# PSSchematic.net
KiCad netlist of a schematic drawn in Altium Designer
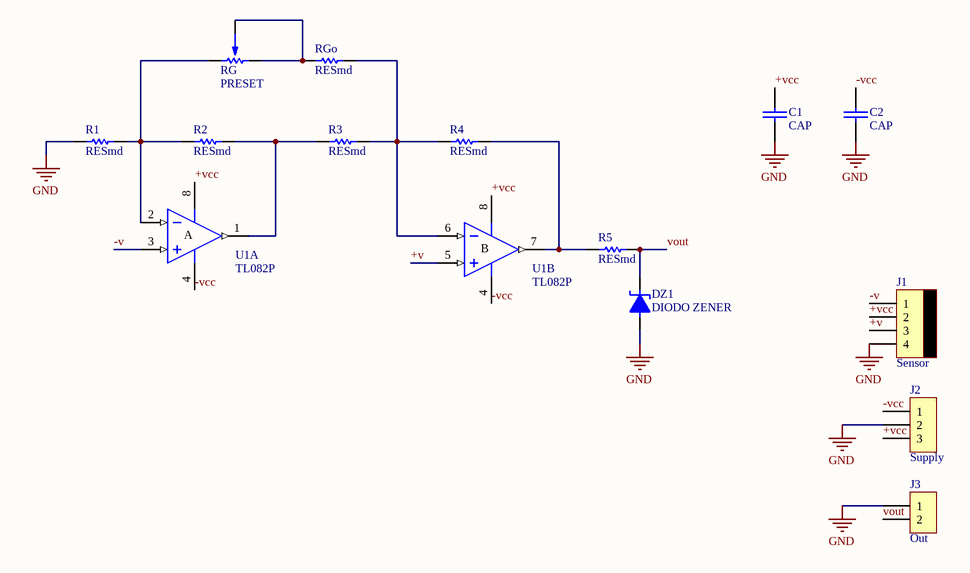
[diagram p0: PSSchematic.SchDoc]

(export (version "E")
  (design (tool "Eeschema 10.0.6"))
  (components
    (comp (ref "C1") (value "CAP") (footprint "CAP100") (libsource (lib "LIBEBAL") (part "CAP")))
    (comp (ref "C2") (value "CAP") (footprint "CAP100") (libsource (lib "LIBEBAL") (part "CAP")))
    (comp (ref "DZ1")
      (value "DIODO ZENER")
      (footprint "DO41")
      (libsource (lib "LIBEBAL") (part "DIODO ZENER"))
    )
    (comp (ref "J1") (value "Sensor") (footprint "MOLEX4") (libsource (lib "LIBEBAL") (part "MOLEX4")))
    (comp (ref "J2") (value "Supply") (footprint "BORNERA3") (libsource (lib "LIBEBAL") (part "BORNERA 3")))
    (comp (ref "J3") (value "Out") (footprint "BORNERA2") (libsource (lib "LIBEBAL") (part "BORNERA 2")))
    (comp (ref "R1") (value "RESmd") (footprint "0805") (libsource (lib "LIBEBAL") (part "RES")))
    (comp (ref "R2") (value "RESmd") (footprint "0805") (libsource (lib "LIBEBAL") (part "RES")))
    (comp (ref "R3") (value "RESmd") (footprint "0805") (libsource (lib "LIBEBAL") (part "RES")))
    (comp (ref "R4") (value "RESmd") (footprint "0805") (libsource (lib "LIBEBAL") (part "RES")))
    (comp (ref "R5") (value "RESmd") (footprint "0805") (libsource (lib "LIBEBAL") (part "RES")))
    (comp (ref "RG") (value "PRESET") (footprint "PRESET V") (libsource (lib "LIBEBAL") (part "PRESET")))
    (comp (ref "RGo") (value "RESmd") (footprint "0805") (libsource (lib "LIBEBAL") (part "RES")))
    (comp (ref "U1")
      (value "TL082P")
      (footprint "P008")
      (description "JFET-Input Operational Amplifier")
      (fields (field (name "PUBLISHER") "Altium Limited"))
      (libsource (lib "TI Operational Amplifier") (part "TL082P"))
    )
  )
  (nets
    (net (code "1") (name "/+v") (class "Default")
      (node (ref "J1") (pin "3") (pinfunction "3_3") (pintype "passive"))
      (node (ref "U1") (pin "5") (pinfunction "IN+_5") (pintype "input"))
    )
    (net (code "2") (name "/+vcc") (class "Default")
      (node (ref "C1") (pin "1") (pinfunction "1_1") (pintype "passive"))
      (node (ref "J1") (pin "2") (pinfunction "2_2") (pintype "passive"))
      (node (ref "J2") (pin "3") (pinfunction "3_3") (pintype "passive"))
      (node (ref "U1") (pin "8") (pinfunction "V+_8") (pintype "power_in"))
    )
    (net (code "3") (name "/-v") (class "Default")
      (node (ref "J1") (pin "1") (pinfunction "1_1") (pintype "passive"))
      (node (ref "U1") (pin "3") (pinfunction "IN+_3") (pintype "input"))
    )
    (net (code "4") (name "/-vcc") (class "Default")
      (node (ref "C2") (pin "1") (pinfunction "1_1") (pintype "passive"))
      (node (ref "J2") (pin "1") (pinfunction "1_1") (pintype "passive"))
      (node (ref "U1") (pin "4") (pinfunction "V-_4") (pintype "power_in"))
    )
    (net (code "5") (name "/vout") (class "Default")
      (node (ref "DZ1") (pin "2") (pinfunction "2_2") (pintype "passive"))
      (node (ref "J3") (pin "2") (pinfunction "2_2") (pintype "passive"))
      (node (ref "R5") (pin "2") (pinfunction "2_2") (pintype "passive"))
    )
    (net (code "6") (name "GND") (class "Default")
      (node (ref "C1") (pin "2") (pinfunction "2_2") (pintype "passive"))
      (node (ref "C2") (pin "2") (pinfunction "2_2") (pintype "passive"))
      (node (ref "DZ1") (pin "1") (pinfunction "1_1") (pintype "passive"))
      (node (ref "J1") (pin "4") (pinfunction "4_4") (pintype "passive"))
      (node (ref "J2") (pin "2") (pinfunction "2_2") (pintype "passive"))
      (node (ref "J3") (pin "1") (pinfunction "1_1") (pintype "passive"))
      (node (ref "R1") (pin "1") (pinfunction "1_1") (pintype "passive"))
    )
    (net (code "7") (name "Net-(RG-Pad2)") (class "Default")
      (node (ref "RG") (pin "2") (pinfunction "2_2") (pintype "passive"))
      (node (ref "RG") (pin "3") (pinfunction "3_3") (pintype "passive"))
      (node (ref "RGo") (pin "1") (pinfunction "1_1") (pintype "passive"))
    )
    (net (code "8") (name "Net-(U1A-IN-)") (class "Default")
      (node (ref "R1") (pin "2") (pinfunction "2_2") (pintype "passive"))
      (node (ref "R2") (pin "1") (pinfunction "1_1") (pintype "passive"))
      (node (ref "RG") (pin "1") (pinfunction "1_1") (pintype "passive"))
      (node (ref "U1") (pin "2") (pinfunction "IN-_2") (pintype "input"))
    )
    (net (code "9") (name "Net-(U1A-OUT)") (class "Default")
      (node (ref "R2") (pin "2") (pinfunction "2_2") (pintype "passive"))
      (node (ref "R3") (pin "1") (pinfunction "1_1") (pintype "passive"))
      (node (ref "U1") (pin "1") (pinfunction "OUT_1") (pintype "output"))
    )
    (net (code "10") (name "Net-(U1B-IN-)") (class "Default")
      (node (ref "R3") (pin "2") (pinfunction "2_2") (pintype "passive"))
      (node (ref "R4") (pin "1") (pinfunction "1_1") (pintype "passive"))
      (node (ref "RGo") (pin "2") (pinfunction "2_2") (pintype "passive"))
      (node (ref "U1") (pin "6") (pinfunction "IN-_6") (pintype "input"))
    )
    (net (code "11") (name "Net-(U1B-OUT)") (class "Default")
      (node (ref "R4") (pin "2") (pinfunction "2_2") (pintype "passive"))
      (node (ref "R5") (pin "1") (pinfunction "1_1") (pintype "passive"))
      (node (ref "U1") (pin "7") (pinfunction "OUT_7") (pintype "output"))
    )
  )
)
